# HeightRuleRoom1_9mm.net
KiCad netlist of a schematic drawn in Altium Designer
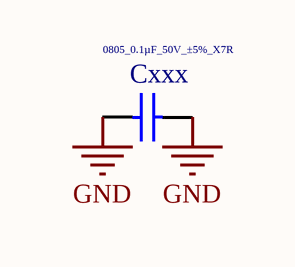
[diagram p0: HeightRuleRoom1.9mm.SchDoc]

(export (version "E")
  (design (tool "Eeschema 10.0.6"))
  (components
    (comp (ref "Cxxx")
      (value "0805_0.1µF_50V_±5%_X7R")
      (footprint "0805C")
      (description "CAP CER 0.1UF 50V 5% X7R 0805")
      (fields (field (name "PART NUMBER") "08055C104JAT2A") (field (name "MANUFACTURER") "AVX Corporation"))
      (libsource (lib "Capacitors") (part "Capacitor"))
    )
  )
  (nets
    (net (code "1") (name "GND") (class "Default")
      (node (ref "Cxxx") (pin "1") (pinfunction "1_1") (pintype "passive"))
      (node (ref "Cxxx") (pin "2") (pinfunction "2_2") (pintype "passive"))
    )
  )
)
